# Poti.net
KiCad netlist of a schematic drawn in EAGLE
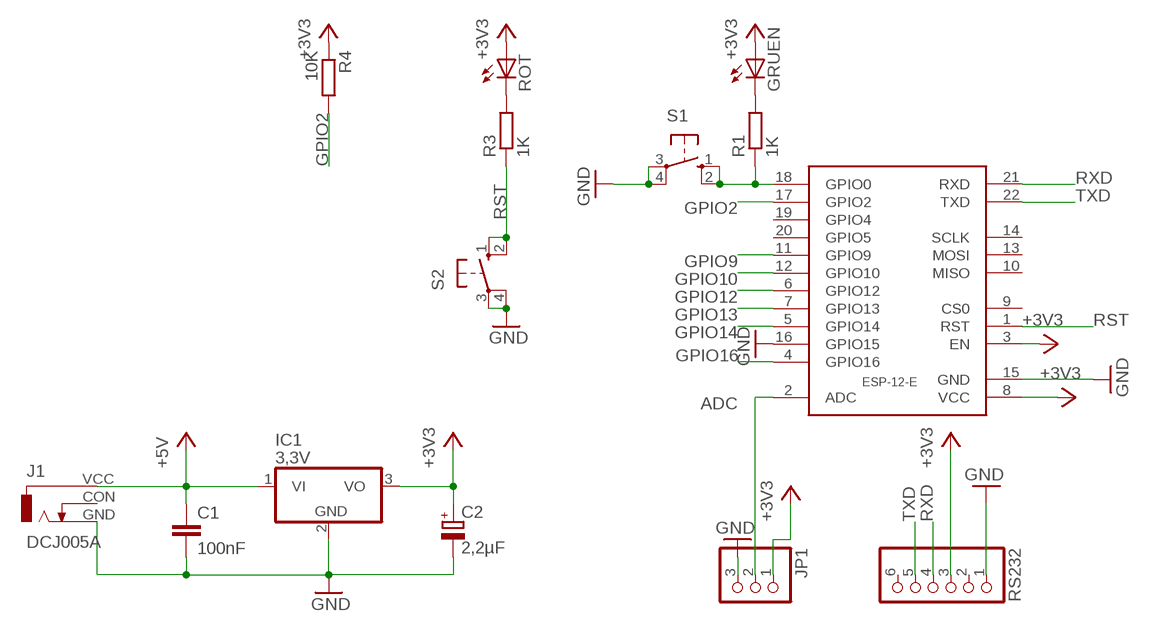
[diagram p0: schematic, sheet 1]

(export (version "E")
  (design (tool "Eeschema 10.0.6"))
  (components
    (comp (ref "C1")
      (value "100nF")
      (footprint "eagle-import:C050-030X075")
      (libsource (lib "eagle-import") (part "C-EU050-030X075"))
    )
    (comp (ref "C2")
      (value "2,2µF")
      (footprint "eagle-import:E2,5-6")
      (libsource (lib "eagle-import") (part "CPOL-EUE2.5-6"))
    )
    (comp (ref "GRUEN")
      (value "LED5MM")
      (footprint "eagle-import:LED5MM")
      (libsource (lib "eagle-import") (part "LED5MM"))
    )
    (comp (ref "IC1")
      (value "3,3V")
      (footprint "eagle-import:TO220V")
      (libsource (lib "eagle-import") (part "78TV05"))
    )
    (comp (ref "J1")
      (value "DCJ005A")
      (footprint "eagle-import:DC005A")
      (libsource (lib "eagle-import") (part "DCJ005A"))
    )
    (comp (ref "JP1")
      (value "PINHD-1X3")
      (footprint "eagle-import:1X03")
      (libsource (lib "eagle-import") (part "PINHD-1X3"))
    )
    (comp (ref "R1")
      (value "1K")
      (footprint "eagle-import:0207_10")
      (libsource (lib "eagle-import") (part "R-EU_0207/10"))
    )
    (comp (ref "R3")
      (value "1K")
      (footprint "eagle-import:0207_10")
      (libsource (lib "eagle-import") (part "R-EU_0207/10"))
    )
    (comp (ref "R4")
      (value "10K")
      (footprint "eagle-import:0207_10")
      (libsource (lib "eagle-import") (part "R-EU_0207/10"))
    )
    (comp (ref "ROT")
      (value "LED5MM")
      (footprint "eagle-import:LED5MM")
      (libsource (lib "eagle-import") (part "LED5MM"))
    )
    (comp (ref "RS232")
      (value "PINHD-1X6")
      (footprint "eagle-import:1X06")
      (libsource (lib "eagle-import") (part "PINHD-1X6"))
    )
    (comp (ref "S1")
      (value "10-XX")
      (footprint "eagle-import:B3F-10XX")
      (fields (field (name "MPN") "B3F-1000"))
      (libsource (lib "eagle-import") (part "10-XX"))
    )
    (comp (ref "S2")
      (value "10-XX")
      (footprint "eagle-import:B3F-10XX")
      (fields (field (name "MPN") "B3F-1000"))
      (libsource (lib "eagle-import") (part "10-XX"))
    )
    (comp (ref "U$1")
      (value "ESP-12-E")
      (footprint "eagle-import:ESP-12-E")
      (libsource (lib "eagle-import") (part "ESP-12-E"))
    )
  )
  (nets
    (net (code "1") (name "+3V3") (class "Default")
      (node (ref "C2") (pin "+") (pinfunction "+_+") (pintype "passive"))
      (node (ref "GRUEN") (pin "A") (pinfunction "A_A") (pintype "passive"))
      (node (ref "IC1") (pin "3") (pinfunction "VO_3") (pintype "passive"))
      (node (ref "JP1") (pin "1") (pinfunction "1_1") (pintype "passive"))
      (node (ref "R4") (pin "1") (pinfunction "1_1") (pintype "passive"))
      (node (ref "ROT") (pin "A") (pinfunction "A_A") (pintype "passive"))
      (node (ref "RS232") (pin "3") (pinfunction "3_3") (pintype "passive"))
      (node (ref "U$1") (pin "3") (pinfunction "EN_3") (pintype "bidirectional"))
      (node (ref "U$1") (pin "8") (pinfunction "VCC_8") (pintype "power_in"))
    )
    (net (code "2") (name "+5V") (class "Default")
      (node (ref "C1") (pin "1") (pinfunction "1_1") (pintype "passive"))
      (node (ref "IC1") (pin "1") (pinfunction "VI_1") (pintype "input"))
      (node (ref "J1") (pin "VCC") (pinfunction "1_VCC") (pintype "passive"))
    )
    (net (code "3") (name "/ADC") (class "Default")
      (node (ref "JP1") (pin "2") (pinfunction "2_2") (pintype "passive"))
      (node (ref "U$1") (pin "2") (pinfunction "ADC_2") (pintype "bidirectional"))
    )
    (net (code "4") (name "/GPIO2") (class "Default")
      (node (ref "R4") (pin "2") (pinfunction "2_2") (pintype "passive"))
      (node (ref "U$1") (pin "17") (pinfunction "GPIO2_17") (pintype "bidirectional"))
    )
    (net (code "5") (name "/GPIO9") (class "Default")
      (node (ref "U$1") (pin "11") (pinfunction "GPIO9_11") (pintype "bidirectional"))
    )
    (net (code "6") (name "/GPIO10") (class "Default")
      (node (ref "U$1") (pin "12") (pinfunction "GPIO10_12") (pintype "bidirectional"))
    )
    (net (code "7") (name "/GPIO12") (class "Default")
      (node (ref "U$1") (pin "6") (pinfunction "GPIO12_6") (pintype "bidirectional"))
    )
    (net (code "8") (name "/GPIO13") (class "Default")
      (node (ref "U$1") (pin "7") (pinfunction "GPIO13_7") (pintype "bidirectional"))
    )
    (net (code "9") (name "/GPIO14") (class "Default")
      (node (ref "U$1") (pin "5") (pinfunction "GPIO14_5") (pintype "bidirectional"))
    )
    (net (code "10") (name "/GPIO16") (class "Default")
      (node (ref "U$1") (pin "4") (pinfunction "GPIO16_4") (pintype "bidirectional"))
    )
    (net (code "11") (name "/RST") (class "Default")
      (node (ref "R3") (pin "1") (pinfunction "1_1") (pintype "passive"))
      (node (ref "S2") (pin "1") (pinfunction "S_1") (pintype "passive"))
      (node (ref "S2") (pin "2") (pinfunction "S1_2") (pintype "passive"))
      (node (ref "U$1") (pin "1") (pinfunction "RST_1") (pintype "bidirectional"))
    )
    (net (code "12") (name "/RXD") (class "Default")
      (node (ref "RS232") (pin "4") (pinfunction "4_4") (pintype "passive"))
      (node (ref "U$1") (pin "21") (pinfunction "RXD_21") (pintype "bidirectional"))
    )
    (net (code "13") (name "/TXD") (class "Default")
      (node (ref "RS232") (pin "5") (pinfunction "5_5") (pintype "passive"))
      (node (ref "U$1") (pin "22") (pinfunction "TXD_22") (pintype "bidirectional"))
    )
    (net (code "14") (name "GND") (class "Default")
      (node (ref "C1") (pin "2") (pinfunction "2_2") (pintype "passive"))
      (node (ref "C2") (pin "-") (pinfunction "-_-") (pintype "passive"))
      (node (ref "IC1") (pin "2") (pinfunction "GND_2") (pintype "passive"))
      (node (ref "J1") (pin "GND") (pinfunction "3_GND") (pintype "passive"))
      (node (ref "JP1") (pin "3") (pinfunction "3_3") (pintype "passive"))
      (node (ref "RS232") (pin "1") (pinfunction "1_1") (pintype "passive"))
      (node (ref "S1") (pin "3") (pinfunction "P_3") (pintype "passive"))
      (node (ref "S1") (pin "4") (pinfunction "P1_4") (pintype "passive"))
      (node (ref "S2") (pin "3") (pinfunction "P_3") (pintype "passive"))
      (node (ref "S2") (pin "4") (pinfunction "P1_4") (pintype "passive"))
      (node (ref "U$1") (pin "15") (pinfunction "GND_15") (pintype "power_in"))
      (node (ref "U$1") (pin "16") (pinfunction "GPIO15_16") (pintype "bidirectional"))
    )
    (net (code "15") (name "Net-(GRUEN-C)") (class "Default")
      (node (ref "GRUEN") (pin "K") (pinfunction "C_K") (pintype "passive"))
      (node (ref "R1") (pin "2") (pinfunction "2_2") (pintype "passive"))
    )
    (net (code "16") (name "Net-(ROT-C)") (class "Default")
      (node (ref "R3") (pin "2") (pinfunction "2_2") (pintype "passive"))
      (node (ref "ROT") (pin "K") (pinfunction "C_K") (pintype "passive"))
    )
    (net (code "17") (name "Net-(S1-S)") (class "Default")
      (node (ref "R1") (pin "1") (pinfunction "1_1") (pintype "passive"))
      (node (ref "S1") (pin "1") (pinfunction "S_1") (pintype "passive"))
      (node (ref "S1") (pin "2") (pinfunction "S1_2") (pintype "passive"))
      (node (ref "U$1") (pin "18") (pinfunction "GPIO0_18") (pintype "bidirectional"))
    )
    (net (code "18") (name "unconnected-(J1-2-PadCON)") (class "Default")
      (node (ref "J1") (pin "CON") (pinfunction "2_CON") (pintype "passive"))
    )
    (net (code "19") (name "unconnected-(RS232-Pad2)") (class "Default")
      (node (ref "RS232") (pin "2") (pinfunction "2_2") (pintype "passive"))
    )
    (net (code "20") (name "unconnected-(RS232-Pad6)") (class "Default")
      (node (ref "RS232") (pin "6") (pinfunction "6_6") (pintype "passive"))
    )
    (net (code "21") (name "unconnected-(U$1-CS0-Pad9)") (class "Default")
      (node (ref "U$1") (pin "9") (pinfunction "CS0_9") (pintype "bidirectional"))
    )
    (net (code "22") (name "unconnected-(U$1-GPIO4-Pad19)") (class "Default")
      (node (ref "U$1") (pin "19") (pinfunction "GPIO4_19") (pintype "bidirectional"))
    )
    (net (code "23") (name "unconnected-(U$1-GPIO5-Pad20)") (class "Default")
      (node (ref "U$1") (pin "20") (pinfunction "GPIO5_20") (pintype "bidirectional"))
    )
    (net (code "24") (name "unconnected-(U$1-MISO-Pad10)") (class "Default")
      (node (ref "U$1") (pin "10") (pinfunction "MISO_10") (pintype "bidirectional"))
    )
    (net (code "25") (name "unconnected-(U$1-MOSI-Pad13)") (class "Default")
      (node (ref "U$1") (pin "13") (pinfunction "MOSI_13") (pintype "bidirectional"))
    )
    (net (code "26") (name "unconnected-(U$1-SCLK-Pad14)") (class "Default")
      (node (ref "U$1") (pin "14") (pinfunction "SCLK_14") (pintype "bidirectional"))
    )
  )
)
